# Thermostat.net
KiCad netlist of a schematic drawn in EAGLE
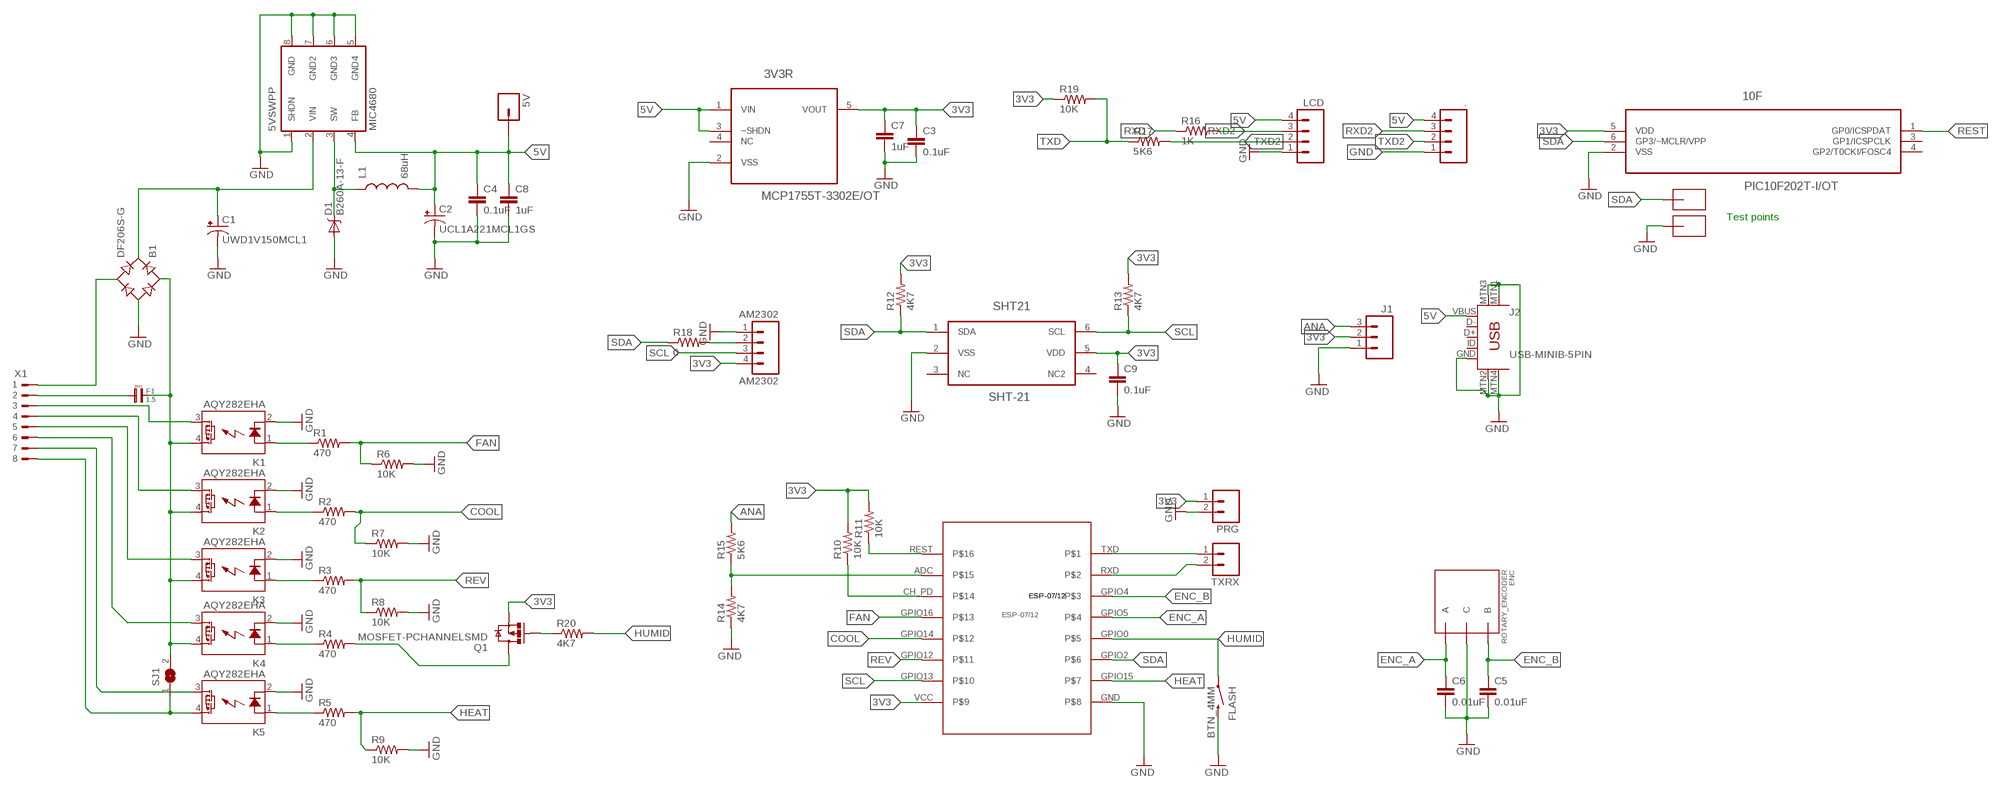
[diagram p0: schematic, sheet 1]

(export (version "E")
  (design (tool "Eeschema 10.0.6"))
  (components
    (comp (ref ".")
      (value "M04PTH")
      (footprint "eagle-import:1X04")
      (libsource (lib "eagle-import") (part "M04PTH"))
    )
    (comp (ref "3V3R")
      (value "MCP1755T-3302E/OT")
      (footprint "eagle-import:SOT95P270X145-5N")
      (fields (field (name "MPN") "MCP1801T-3302I/OT"))
      (libsource (lib "eagle-import") (part "MCP1801T-3302I/OT"))
    )
    (comp (ref "5V")
      (value "M01PTH")
      (footprint "eagle-import:1X01")
      (libsource (lib "eagle-import") (part "M01PTH"))
    )
    (comp (ref "5VSWPP")
      (value "MIC4680")
      (footprint "eagle-import:SO08")
      (libsource (lib "eagle-import") (part "MIC4680"))
    )
    (comp (ref "10F")
      (value "PIC10F202T-I/OT")
      (footprint "eagle-import:SOT95P270X145-6N")
      (libsource (lib "eagle-import") (part "PIC10F202T-I/OT"))
    )
    (comp (ref "AM2302")
      (value "AM2302")
      (footprint "eagle-import:1X04")
      (libsource (lib "eagle-import") (part "M04PTH"))
    )
    (comp (ref "B1")
      (value "DF206S-G")
      (footprint "eagle-import:DFS")
      (libsource (lib "eagle-import") (part "DFS01"))
    )
    (comp (ref "C1")
      (value "UWD1V150MCL1")
      (footprint "eagle-import:PANASONIC_C")
      (libsource (lib "eagle-import") (part "CAP_POLC"))
    )
    (comp (ref "C2")
      (value "UCL1A221MCL1GS")
      (footprint "eagle-import:PANASONIC_D")
      (libsource (lib "eagle-import") (part "CAP_POLD"))
    )
    (comp (ref "C3")
      (value "0.1uF")
      (footprint "eagle-import:0805")
      (libsource (lib "eagle-import") (part "CAP0805"))
    )
    (comp (ref "C4")
      (value "0.1uF")
      (footprint "eagle-import:0805")
      (libsource (lib "eagle-import") (part "CAP0805"))
    )
    (comp (ref "C5")
      (value "0.01uF")
      (footprint "eagle-import:0805")
      (libsource (lib "eagle-import") (part "CAP0805"))
    )
    (comp (ref "C6")
      (value "0.01uF")
      (footprint "eagle-import:0805")
      (libsource (lib "eagle-import") (part "CAP0805"))
    )
    (comp (ref "C7")
      (value "1uF")
      (footprint "eagle-import:0805")
      (libsource (lib "eagle-import") (part "CAP0805"))
    )
    (comp (ref "C8")
      (value "1uF")
      (footprint "eagle-import:0805")
      (libsource (lib "eagle-import") (part "CAP0805"))
    )
    (comp (ref "C9")
      (value "0.1uF")
      (footprint "eagle-import:0805")
      (libsource (lib "eagle-import") (part "CAP0805"))
    )
    (comp (ref "D1")
      (value "B260A-13-F")
      (footprint "eagle-import:SMA-DIODE")
      (libsource (lib "eagle-import") (part "DIODE-SCHOTTKY_"))
    )
    (comp (ref "ENC")
      (value "ROTARY_ENCODER")
      (footprint "eagle-import:ROTORY_ENC")
      (libsource (lib "eagle-import") (part "ROTARY_ENCODER"))
    )
    (comp (ref "F1")
      (value "1.5")
      (footprint "eagle-import:L4,8")
      (libsource (lib "eagle-import") (part "0,1ÂµF"))
    )
    (comp (ref "FLASH")
      (value "BTN_4MM")
      (footprint "eagle-import:BTN_4MM")
      (libsource (lib "eagle-import") (part "BTN_4MM"))
    )
    (comp (ref "J1")
      (value "M03PTH")
      (footprint "eagle-import:1X03")
      (libsource (lib "eagle-import") (part "M03PTH"))
    )
    (comp (ref "J2")
      (value "USB-MINIB-5PIN")
      (footprint "eagle-import:USB-MINIB")
      (libsource (lib "eagle-import") (part "USB-MINIB-5PIN"))
    )
    (comp (ref "K1")
      (value "AQY282EHA")
      (footprint "eagle-import:SOP04")
      (libsource (lib "eagle-import") (part "AQYSOP22"))
    )
    (comp (ref "K2")
      (value "AQY282EHA")
      (footprint "eagle-import:SOP04")
      (libsource (lib "eagle-import") (part "AQYSOP22"))
    )
    (comp (ref "K3")
      (value "AQY282EHA")
      (footprint "eagle-import:SOP04")
      (libsource (lib "eagle-import") (part "AQYSOP22"))
    )
    (comp (ref "K4")
      (value "AQY282EHA")
      (footprint "eagle-import:SOP04")
      (libsource (lib "eagle-import") (part "AQYSOP22"))
    )
    (comp (ref "K5")
      (value "AQY282EHA")
      (footprint "eagle-import:SOP04")
      (libsource (lib "eagle-import") (part "AQYSOP22"))
    )
    (comp (ref "L1")
      (value "68uH")
      (footprint "eagle-import:DR1030")
      (libsource (lib "eagle-import") (part "INDUCTORDR1030"))
    )
    (comp (ref "LCD")
      (value "M04PTH")
      (footprint "eagle-import:1X04")
      (libsource (lib "eagle-import") (part "M04PTH"))
    )
    (comp (ref "PRG")
      (value "M02PTH")
      (footprint "eagle-import:1X02")
      (libsource (lib "eagle-import") (part "M02PTH"))
    )
    (comp (ref "Q1")
      (value "MOSFET-PCHANNELSMD")
      (footprint "eagle-import:SOT23-3")
      (libsource (lib "eagle-import") (part "MOSFET-PCHANNELSMD"))
    )
    (comp (ref "R1")
      (value "470")
      (footprint "eagle-import:0805")
      (libsource (lib "eagle-import") (part "RESISTOR0805-RES"))
    )
    (comp (ref "R2")
      (value "470")
      (footprint "eagle-import:0805")
      (libsource (lib "eagle-import") (part "RESISTOR0805-RES"))
    )
    (comp (ref "R3")
      (value "470")
      (footprint "eagle-import:0805")
      (libsource (lib "eagle-import") (part "RESISTOR0805-RES"))
    )
    (comp (ref "R4")
      (value "470")
      (footprint "eagle-import:0805")
      (libsource (lib "eagle-import") (part "RESISTOR0805-RES"))
    )
    (comp (ref "R5")
      (value "470")
      (footprint "eagle-import:0805")
      (libsource (lib "eagle-import") (part "RESISTOR0805-RES"))
    )
    (comp (ref "R6")
      (value "10K")
      (footprint "eagle-import:0805")
      (libsource (lib "eagle-import") (part "RESISTOR0805-RES"))
    )
    (comp (ref "R7")
      (value "10K")
      (footprint "eagle-import:0805")
      (libsource (lib "eagle-import") (part "RESISTOR0805-RES"))
    )
    (comp (ref "R8")
      (value "10K")
      (footprint "eagle-import:0805")
      (libsource (lib "eagle-import") (part "RESISTOR0805-RES"))
    )
    (comp (ref "R9")
      (value "10K")
      (footprint "eagle-import:0805")
      (libsource (lib "eagle-import") (part "RESISTOR0805-RES"))
    )
    (comp (ref "R10")
      (value "10K")
      (footprint "eagle-import:0805")
      (libsource (lib "eagle-import") (part "SparkFun-Resistors_RESISTOR0805-RES"))
    )
    (comp (ref "R11")
      (value "10K")
      (footprint "eagle-import:0805")
      (libsource (lib "eagle-import") (part "SparkFun-Resistors_RESISTOR0805-RES"))
    )
    (comp (ref "R12")
      (value "4K7")
      (footprint "eagle-import:0805")
      (libsource (lib "eagle-import") (part "SparkFun-Resistors_RESISTOR0805-RES"))
    )
    (comp (ref "R13")
      (value "4K7")
      (footprint "eagle-import:0805")
      (libsource (lib "eagle-import") (part "SparkFun-Resistors_RESISTOR0805-RES"))
    )
    (comp (ref "R14")
      (value "4K7")
      (footprint "eagle-import:0805")
      (libsource (lib "eagle-import") (part "SparkFun-Resistors_RESISTOR0805-RES"))
    )
    (comp (ref "R15")
      (value "5K6")
      (footprint "eagle-import:0805")
      (libsource (lib "eagle-import") (part "SparkFun-Resistors_RESISTOR0805-RES"))
    )
    (comp (ref "R16")
      (value "1K")
      (footprint "eagle-import:0805")
      (libsource (lib "eagle-import") (part "SparkFun-Resistors_RESISTOR0805-RES"))
    )
    (comp (ref "R17")
      (value "5K6")
      (footprint "eagle-import:0805")
      (libsource (lib "eagle-import") (part "SparkFun-Resistors_RESISTOR0805-RES"))
    )
    (comp (ref "R18")
      (value "0")
      (footprint "eagle-import:0805")
      (libsource (lib "eagle-import") (part "SparkFun-Resistors_RESISTOR0805-RES"))
    )
    (comp (ref "R19")
      (value "10K")
      (footprint "eagle-import:0805")
      (libsource (lib "eagle-import") (part "SparkFun-Resistors_RESISTOR0805-RES"))
    )
    (comp (ref "R20")
      (value "4K7")
      (footprint "eagle-import:0805")
      (libsource (lib "eagle-import") (part "RESISTOR0805-RES"))
    )
    (comp (ref "SHT21")
      (value "SHT-21")
      (footprint "eagle-import:SHT21")
      (libsource (lib "eagle-import") (part "SHT-21"))
    )
    (comp (ref "SJ1") (value "SJ") (footprint "eagle-import:SJ") (libsource (lib "eagle-import") (part "SJ")))
    (comp (ref "TXRX")
      (value "M02PTH")
      (footprint "eagle-import:1X02")
      (libsource (lib "eagle-import") (part "M02PTH"))
    )
    (comp (ref "U$1")
      (value "ESP-07/12")
      (footprint "eagle-import:ESP-07_12")
      (libsource (lib "eagle-import") (part "ESP-07/12"))
    )
    (comp (ref "U$2")
      (value "SMD-PAD1")
      (footprint "eagle-import:SMD-PAD1")
      (libsource (lib "eagle-import") (part "SMD-PAD1"))
    )
    (comp (ref "U$5")
      (value "SMD-PAD1")
      (footprint "eagle-import:SMD-PAD1")
      (libsource (lib "eagle-import") (part "SMD-PAD1"))
    )
    (comp (ref "X1")
      (value "180-8")
      (footprint "eagle-import:180-8")
      (libsource (lib "eagle-import") (part "180-8"))
    )
  )
  (nets
    (net (code "1") (name "/NC") (class "Default")
      (node (ref "SHT21") (pin "3") (pinfunction "NC_3") (pintype "power_in"))
    )
    (net (code "2") (name "3V3") (class "Default")
      (node (ref "10F") (pin "5") (pinfunction "VDD_5") (pintype "power_in"))
      (node (ref "3V3R") (pin "5") (pinfunction "VOUT_5") (pintype "output"))
      (node (ref "AM2302") (pin "4") (pinfunction "4_4") (pintype "passive"))
      (node (ref "C3") (pin "1") (pinfunction "1_1") (pintype "passive"))
      (node (ref "C7") (pin "1") (pinfunction "1_1") (pintype "passive"))
      (node (ref "C9") (pin "1") (pinfunction "1_1") (pintype "passive"))
      (node (ref "J1") (pin "2") (pinfunction "2_2") (pintype "passive"))
      (node (ref "PRG") (pin "1") (pinfunction "1_1") (pintype "passive"))
      (node (ref "Q1") (pin "2") (pinfunction "S_2") (pintype "passive"))
      (node (ref "R10") (pin "2") (pinfunction "2_2") (pintype "passive"))
      (node (ref "R11") (pin "2") (pinfunction "2_2") (pintype "passive"))
      (node (ref "R12") (pin "2") (pinfunction "2_2") (pintype "passive"))
      (node (ref "R13") (pin "2") (pinfunction "2_2") (pintype "passive"))
      (node (ref "R19") (pin "1") (pinfunction "1_1") (pintype "passive"))
      (node (ref "SHT21") (pin "5") (pinfunction "VDD_5") (pintype "bidirectional"))
      (node (ref "U$1") (pin "VCC") (pinfunction "P$9_VCC") (pintype "bidirectional"))
    )
    (net (code "3") (name "5V") (class "Default")
      (node (ref ".") (pin "4") (pinfunction "4_4") (pintype "passive"))
      (node (ref "3V3R") (pin "1") (pinfunction "VIN_1") (pintype "power_in"))
      (node (ref "3V3R") (pin "3") (pinfunction "~{SHDN}_3") (pintype "input"))
      (node (ref "5V") (pin "1") (pinfunction "1_1") (pintype "passive"))
      (node (ref "5VSWPP") (pin "4") (pinfunction "FB_4") (pintype "power_in"))
      (node (ref "C2") (pin "+") (pinfunction "+_+") (pintype "passive"))
      (node (ref "C4") (pin "1") (pinfunction "1_1") (pintype "passive"))
      (node (ref "C8") (pin "1") (pinfunction "1_1") (pintype "passive"))
      (node (ref "J2") (pin "VBUS") (pinfunction "VBUS_VBUS") (pintype "bidirectional"))
      (node (ref "L1") (pin "2") (pinfunction "2_2") (pintype "passive"))
      (node (ref "LCD") (pin "4") (pinfunction "4_4") (pintype "passive"))
    )
    (net (code "4") (name "ANA") (class "Default")
      (node (ref "J1") (pin "3") (pinfunction "3_3") (pintype "passive"))
      (node (ref "R15") (pin "2") (pinfunction "2_2") (pintype "passive"))
    )
    (net (code "5") (name "COOL") (class "Default")
      (node (ref "R2") (pin "2") (pinfunction "2_2") (pintype "passive"))
      (node (ref "R7") (pin "1") (pinfunction "1_1") (pintype "passive"))
      (node (ref "U$1") (pin "GPIO14") (pinfunction "P$12_GPIO14") (pintype "bidirectional"))
    )
    (net (code "6") (name "ENC_A") (class "Default")
      (node (ref "C6") (pin "1") (pinfunction "1_1") (pintype "passive"))
      (node (ref "ENC") (pin "A") (pinfunction "A_A") (pintype "bidirectional"))
      (node (ref "U$1") (pin "GPIO5") (pinfunction "P$4_GPIO5") (pintype "bidirectional"))
    )
    (net (code "7") (name "ENC_B") (class "Default")
      (node (ref "C5") (pin "1") (pinfunction "1_1") (pintype "passive"))
      (node (ref "ENC") (pin "B") (pinfunction "B_B") (pintype "bidirectional"))
      (node (ref "U$1") (pin "GPIO4") (pinfunction "P$3_GPIO4") (pintype "bidirectional"))
    )
    (net (code "8") (name "FAN") (class "Default")
      (node (ref "R1") (pin "2") (pinfunction "2_2") (pintype "passive"))
      (node (ref "R6") (pin "1") (pinfunction "1_1") (pintype "passive"))
      (node (ref "U$1") (pin "GPIO16") (pinfunction "P$13_GPIO16") (pintype "bidirectional"))
    )
    (net (code "9") (name "GND") (class "Default")
      (node (ref ".") (pin "1") (pinfunction "1_1") (pintype "passive"))
      (node (ref "10F") (pin "2") (pinfunction "VSS_2") (pintype "power_in"))
      (node (ref "3V3R") (pin "2") (pinfunction "VSS_2") (pintype "passive"))
      (node (ref "5VSWPP") (pin "1") (pinfunction "SHDN_1") (pintype "output"))
      (node (ref "5VSWPP") (pin "5") (pinfunction "GND4_5") (pintype "output"))
      (node (ref "5VSWPP") (pin "6") (pinfunction "GND3_6") (pintype "input"))
      (node (ref "5VSWPP") (pin "7") (pinfunction "GND2_7") (pintype "output"))
      (node (ref "5VSWPP") (pin "8") (pinfunction "GND_8") (pintype "passive"))
      (node (ref "AM2302") (pin "1") (pinfunction "1_1") (pintype "passive"))
      (node (ref "B1") (pin "-") (pinfunction "-_-") (pintype "passive"))
      (node (ref "C1") (pin "-") (pinfunction "-_-") (pintype "passive"))
      (node (ref "C2") (pin "-") (pinfunction "-_-") (pintype "passive"))
      (node (ref "C3") (pin "2") (pinfunction "2_2") (pintype "passive"))
      (node (ref "C4") (pin "2") (pinfunction "2_2") (pintype "passive"))
      (node (ref "C5") (pin "2") (pinfunction "2_2") (pintype "passive"))
      (node (ref "C6") (pin "2") (pinfunction "2_2") (pintype "passive"))
      (node (ref "C7") (pin "2") (pinfunction "2_2") (pintype "passive"))
      (node (ref "C8") (pin "2") (pinfunction "2_2") (pintype "passive"))
      (node (ref "C9") (pin "2") (pinfunction "2_2") (pintype "passive"))
      (node (ref "D1") (pin "A") (pinfunction "A_A") (pintype "passive"))
      (node (ref "ENC") (pin "C") (pinfunction "C_C") (pintype "bidirectional"))
      (node (ref "FLASH") (pin "2") (pinfunction "2_2") (pintype "passive"))
      (node (ref "J1") (pin "1") (pinfunction "1_1") (pintype "passive"))
      (node (ref "J2") (pin "GND") (pinfunction "GND_GND") (pintype "bidirectional"))
      (node (ref "J2") (pin "MTN1") (pinfunction "MTN2_MTN1") (pintype "bidirectional"))
      (node (ref "J2") (pin "MTN2") (pinfunction "MTN3_MTN2") (pintype "bidirectional"))
      (node (ref "J2") (pin "MTN3") (pinfunction "MTN1_MTN3") (pintype "bidirectional"))
      (node (ref "J2") (pin "MTN4") (pinfunction "MTN4_MTN4") (pintype "bidirectional"))
      (node (ref "K1") (pin "2") (pinfunction "K_2") (pintype "passive"))
      (node (ref "K2") (pin "2") (pinfunction "K_2") (pintype "passive"))
      (node (ref "K3") (pin "2") (pinfunction "K_2") (pintype "passive"))
      (node (ref "K4") (pin "2") (pinfunction "K_2") (pintype "passive"))
      (node (ref "K5") (pin "2") (pinfunction "K_2") (pintype "passive"))
      (node (ref "LCD") (pin "1") (pinfunction "1_1") (pintype "passive"))
      (node (ref "PRG") (pin "2") (pinfunction "2_2") (pintype "passive"))
      (node (ref "R14") (pin "1") (pinfunction "1_1") (pintype "passive"))
      (node (ref "R6") (pin "2") (pinfunction "2_2") (pintype "passive"))
      (node (ref "R7") (pin "2") (pinfunction "2_2") (pintype "passive"))
      (node (ref "R8") (pin "2") (pinfunction "2_2") (pintype "passive"))
      (node (ref "R9") (pin "2") (pinfunction "2_2") (pintype "passive"))
      (node (ref "SHT21") (pin "2") (pinfunction "VSS_2") (pintype "input"))
      (node (ref "U$1") (pin "GND") (pinfunction "P$8_GND") (pintype "bidirectional"))
      (node (ref "U$2") (pin ">NAME") (pinfunction "P$1_>NAME") (pintype "bidirectional"))
    )
    (net (code "10") (name "HEAT") (class "Default")
      (node (ref "R5") (pin "2") (pinfunction "2_2") (pintype "passive"))
      (node (ref "R9") (pin "1") (pinfunction "1_1") (pintype "passive"))
      (node (ref "U$1") (pin "GPIO15") (pinfunction "P$7_GPIO15") (pintype "bidirectional"))
    )
    (net (code "11") (name "HUMID") (class "Default")
      (node (ref "FLASH") (pin "1") (pinfunction "1_1") (pintype "passive"))
      (node (ref "R20") (pin "2") (pinfunction "2_2") (pintype "passive"))
      (node (ref "U$1") (pin "GPIO0") (pinfunction "P$5_GPIO0") (pintype "bidirectional"))
    )
    (net (code "12") (name "Net-(5VSWPP-SW)") (class "Default")
      (node (ref "5VSWPP") (pin "3") (pinfunction "SW_3") (pintype "input"))
      (node (ref "D1") (pin "C") (pinfunction "C_C") (pintype "passive"))
      (node (ref "L1") (pin "1") (pinfunction "1_1") (pintype "passive"))
    )
    (net (code "13") (name "Net-(5VSWPP-VIN)") (class "Default")
      (node (ref "5VSWPP") (pin "2") (pinfunction "VIN_2") (pintype "input"))
      (node (ref "B1") (pin "+") (pinfunction "+_+") (pintype "passive"))
      (node (ref "C1") (pin "+") (pinfunction "+_+") (pintype "passive"))
    )
    (net (code "14") (name "Net-(AM2302-Pad2)") (class "Default")
      (node (ref "AM2302") (pin "2") (pinfunction "2_2") (pintype "passive"))
      (node (ref "R18") (pin "2") (pinfunction "2_2") (pintype "passive"))
    )
    (net (code "15") (name "Net-(B1-PadAC2)") (class "Default")
      (node (ref "B1") (pin "AC2") (pinfunction "AC2_AC2") (pintype "passive"))
      (node (ref "X1") (pin "1") (pinfunction "1_1") (pintype "passive"))
    )
    (net (code "16") (name "Net-(F1-1)") (class "Default")
      (node (ref "F1") (pin "P$1") (pinfunction "1_P$1") (pintype "passive"))
      (node (ref "X1") (pin "2") (pinfunction "2_2") (pintype "passive"))
    )
    (net (code "17") (name "Net-(F1-2)") (class "Default")
      (node (ref "B1") (pin "AC1") (pinfunction "AC1_AC1") (pintype "passive"))
      (node (ref "F1") (pin "P$2") (pinfunction "2_P$2") (pintype "passive"))
      (node (ref "K1") (pin "4") (pinfunction "DS1_4") (pintype "passive"))
      (node (ref "K2") (pin "4") (pinfunction "DS1_4") (pintype "passive"))
      (node (ref "K3") (pin "4") (pinfunction "DS1_4") (pintype "passive"))
      (node (ref "K4") (pin "4") (pinfunction "DS1_4") (pintype "passive"))
      (node (ref "SJ1") (pin "2") (pinfunction "2_2") (pintype "passive"))
    )
    (net (code "18") (name "Net-(K1-A)") (class "Default")
      (node (ref "K1") (pin "1") (pinfunction "A_1") (pintype "passive"))
      (node (ref "R1") (pin "1") (pinfunction "1_1") (pintype "passive"))
    )
    (net (code "19") (name "Net-(K1-DS2)") (class "Default")
      (node (ref "K1") (pin "3") (pinfunction "DS2_3") (pintype "passive"))
      (node (ref "X1") (pin "3") (pinfunction "3_3") (pintype "passive"))
    )
    (net (code "20") (name "Net-(K2-A)") (class "Default")
      (node (ref "K2") (pin "1") (pinfunction "A_1") (pintype "passive"))
      (node (ref "R2") (pin "1") (pinfunction "1_1") (pintype "passive"))
    )
    (net (code "21") (name "Net-(K2-DS2)") (class "Default")
      (node (ref "K2") (pin "3") (pinfunction "DS2_3") (pintype "passive"))
      (node (ref "X1") (pin "4") (pinfunction "4_4") (pintype "passive"))
    )
    (net (code "22") (name "Net-(K3-A)") (class "Default")
      (node (ref "K3") (pin "1") (pinfunction "A_1") (pintype "passive"))
      (node (ref "R3") (pin "1") (pinfunction "1_1") (pintype "passive"))
    )
    (net (code "23") (name "Net-(K3-DS2)") (class "Default")
      (node (ref "K3") (pin "3") (pinfunction "DS2_3") (pintype "passive"))
      (node (ref "X1") (pin "5") (pinfunction "5_5") (pintype "passive"))
    )
    (net (code "24") (name "Net-(K4-A)") (class "Default")
      (node (ref "K4") (pin "1") (pinfunction "A_1") (pintype "passive"))
      (node (ref "R4") (pin "1") (pinfunction "1_1") (pintype "passive"))
    )
    (net (code "25") (name "Net-(K4-DS2)") (class "Default")
      (node (ref "K4") (pin "3") (pinfunction "DS2_3") (pintype "passive"))
      (node (ref "X1") (pin "6") (pinfunction "6_6") (pintype "passive"))
    )
    (net (code "26") (name "Net-(K5-A)") (class "Default")
      (node (ref "K5") (pin "1") (pinfunction "A_1") (pintype "passive"))
      (node (ref "R5") (pin "1") (pinfunction "1_1") (pintype "passive"))
    )
    (net (code "27") (name "Net-(K5-DS1)") (class "Default")
      (node (ref "K5") (pin "4") (pinfunction "DS1_4") (pintype "passive"))
      (node (ref "SJ1") (pin "1") (pinfunction "1_1") (pintype "passive"))
      (node (ref "X1") (pin "8") (pinfunction "8_8") (pintype "passive"))
    )
    (net (code "28") (name "Net-(K5-DS2)") (class "Default")
      (node (ref "K5") (pin "3") (pinfunction "DS2_3") (pintype "passive"))
      (node (ref "X1") (pin "7") (pinfunction "7_7") (pintype "passive"))
    )
    (net (code "29") (name "Net-(Q1-D)") (class "Default")
      (node (ref "Q1") (pin "3") (pinfunction "D_3") (pintype "passive"))
      (node (ref "R4") (pin "2") (pinfunction "2_2") (pintype "passive"))
    )
    (net (code "30") (name "Net-(Q1-G)") (class "Default")
      (node (ref "Q1") (pin "1") (pinfunction "G_1") (pintype "passive"))
      (node (ref "R20") (pin "1") (pinfunction "1_1") (pintype "passive"))
    )
    (net (code "31") (name "Net-(U$1-P$14)") (class "Default")
      (node (ref "R10") (pin "1") (pinfunction "1_1") (pintype "passive"))
      (node (ref "U$1") (pin "CH_PD") (pinfunction "P$14_CH_PD") (pintype "bidirectional"))
    )
    (net (code "32") (name "Net-(U$1-P$15)") (class "Default")
      (node (ref "R14") (pin "2") (pinfunction "2_2") (pintype "passive"))
      (node (ref "R15") (pin "1") (pinfunction "1_1") (pintype "passive"))
      (node (ref "U$1") (pin "ADC") (pinfunction "P$15_ADC") (pintype "bidirectional"))
    )
    (net (code "33") (name "REST") (class "Default")
      (node (ref "10F") (pin "1") (pinfunction "GP0/ICSPDAT_1") (pintype "bidirectional"))
      (node (ref "R11") (pin "1") (pinfunction "1_1") (pintype "passive"))
      (node (ref "U$1") (pin "REST") (pinfunction "P$16_REST") (pintype "bidirectional"))
    )
    (net (code "34") (name "REV") (class "Default")
      (node (ref "R3") (pin "2") (pinfunction "2_2") (pintype "passive"))
      (node (ref "R8") (pin "1") (pinfunction "1_1") (pintype "passive"))
      (node (ref "U$1") (pin "GPIO12") (pinfunction "P$11_GPIO12") (pintype "bidirectional"))
    )
    (net (code "35") (name "RXD") (class "Default")
      (node (ref "R16") (pin "1") (pinfunction "1_1") (pintype "passive"))
      (node (ref "TXRX") (pin "2") (pinfunction "2_2") (pintype "passive"))
      (node (ref "U$1") (pin "RXD") (pinfunction "P$2_RXD") (pintype "bidirectional"))
    )
    (net (code "36") (name "RXD2") (class "Default")
      (node (ref ".") (pin "3") (pinfunction "3_3") (pintype "passive"))
      (node (ref "LCD") (pin "3") (pinfunction "3_3") (pintype "passive"))
      (node (ref "R16") (pin "2") (pinfunction "2_2") (pintype "passive"))
    )
    (net (code "37") (name "SCL") (class "Default")
      (node (ref "AM2302") (pin "3") (pinfunction "3_3") (pintype "passive"))
      (node (ref "R13") (pin "1") (pinfunction "1_1") (pintype "passive"))
      (node (ref "SHT21") (pin "6") (pinfunction "SCL_6") (pintype "bidirectional"))
      (node (ref "U$1") (pin "GPIO13") (pinfunction "P$10_GPIO13") (pintype "bidirectional"))
    )
    (net (code "38") (name "SDA") (class "Default")
      (node (ref "10F") (pin "6") (pinfunction "GP3/~{MCLR/VPP}_6") (pintype "input"))
      (node (ref "R12") (pin "1") (pinfunction "1_1") (pintype "passive"))
      (node (ref "R18") (pin "1") (pinfunction "1_1") (pintype "passive"))
      (node (ref "SHT21") (pin "1") (pinfunction "SDA_1") (pintype "power_in"))
      (node (ref "U$1") (pin "GPIO2") (pinfunction "P$6_GPIO2") (pintype "bidirectional"))
      (node (ref "U$5") (pin ">NAME") (pinfunction "P$1_>NAME") (pintype "bidirectional"))
    )
    (net (code "39") (name "TXD") (class "Default")
      (node (ref "R17") (pin "1") (pinfunction "1_1") (pintype "passive"))
      (node (ref "R19") (pin "2") (pinfunction "2_2") (pintype "passive"))
      (node (ref "TXRX") (pin "1") (pinfunction "1_1") (pintype "passive"))
      (node (ref "U$1") (pin "TXD") (pinfunction "P$1_TXD") (pintype "bidirectional"))
    )
    (net (code "40") (name "TXD2") (class "Default")
      (node (ref ".") (pin "2") (pinfunction "2_2") (pintype "passive"))
      (node (ref "LCD") (pin "2") (pinfunction "2_2") (pintype "passive"))
      (node (ref "R17") (pin "2") (pinfunction "2_2") (pintype "passive"))
    )
    (net (code "41") (name "unconnected-(3V3R-NC-Pad4)") (class "Default")
      (node (ref "3V3R") (pin "4") (pinfunction "NC_4") (pintype "no_connect"))
    )
    (net (code "42") (name "unconnected-(10F-GP1{slash}ICSPCLK-Pad3)") (class "Default")
      (node (ref "10F") (pin "3") (pinfunction "GP1/ICSPCLK_3") (pintype "bidirectional"))
    )
    (net (code "43") (name "unconnected-(10F-GP2{slash}T0CKI{slash}FOSC4-Pad4)") (class "Default")
      (node (ref "10F") (pin "4") (pinfunction "GP2/T0CKI/FOSC4_4") (pintype "bidirectional"))
    )
    (net (code "44") (name "unconnected-(J2-PadD+)") (class "Default")
      (node (ref "J2") (pin "D+") (pinfunction "D+_D+") (pintype "bidirectional"))
    )
    (net (code "45") (name "unconnected-(J2-PadD-)") (class "Default")
      (node (ref "J2") (pin "D-") (pinfunction "D-_D-") (pintype "bidirectional"))
    )
    (net (code "46") (name "unconnected-(J2-PadID)") (class "Default")
      (node (ref "J2") (pin "ID") (pinfunction "ID_ID") (pintype "bidirectional"))
    )
    (net (code "47") (name "unconnected-(SHT21-NC2-Pad4)") (class "Default")
      (node (ref "SHT21") (pin "4") (pinfunction "NC2_4") (pintype "bidirectional"))
    )
  )
)
